# MCU2.net
KiCad netlist of a schematic drawn in Altium Designer
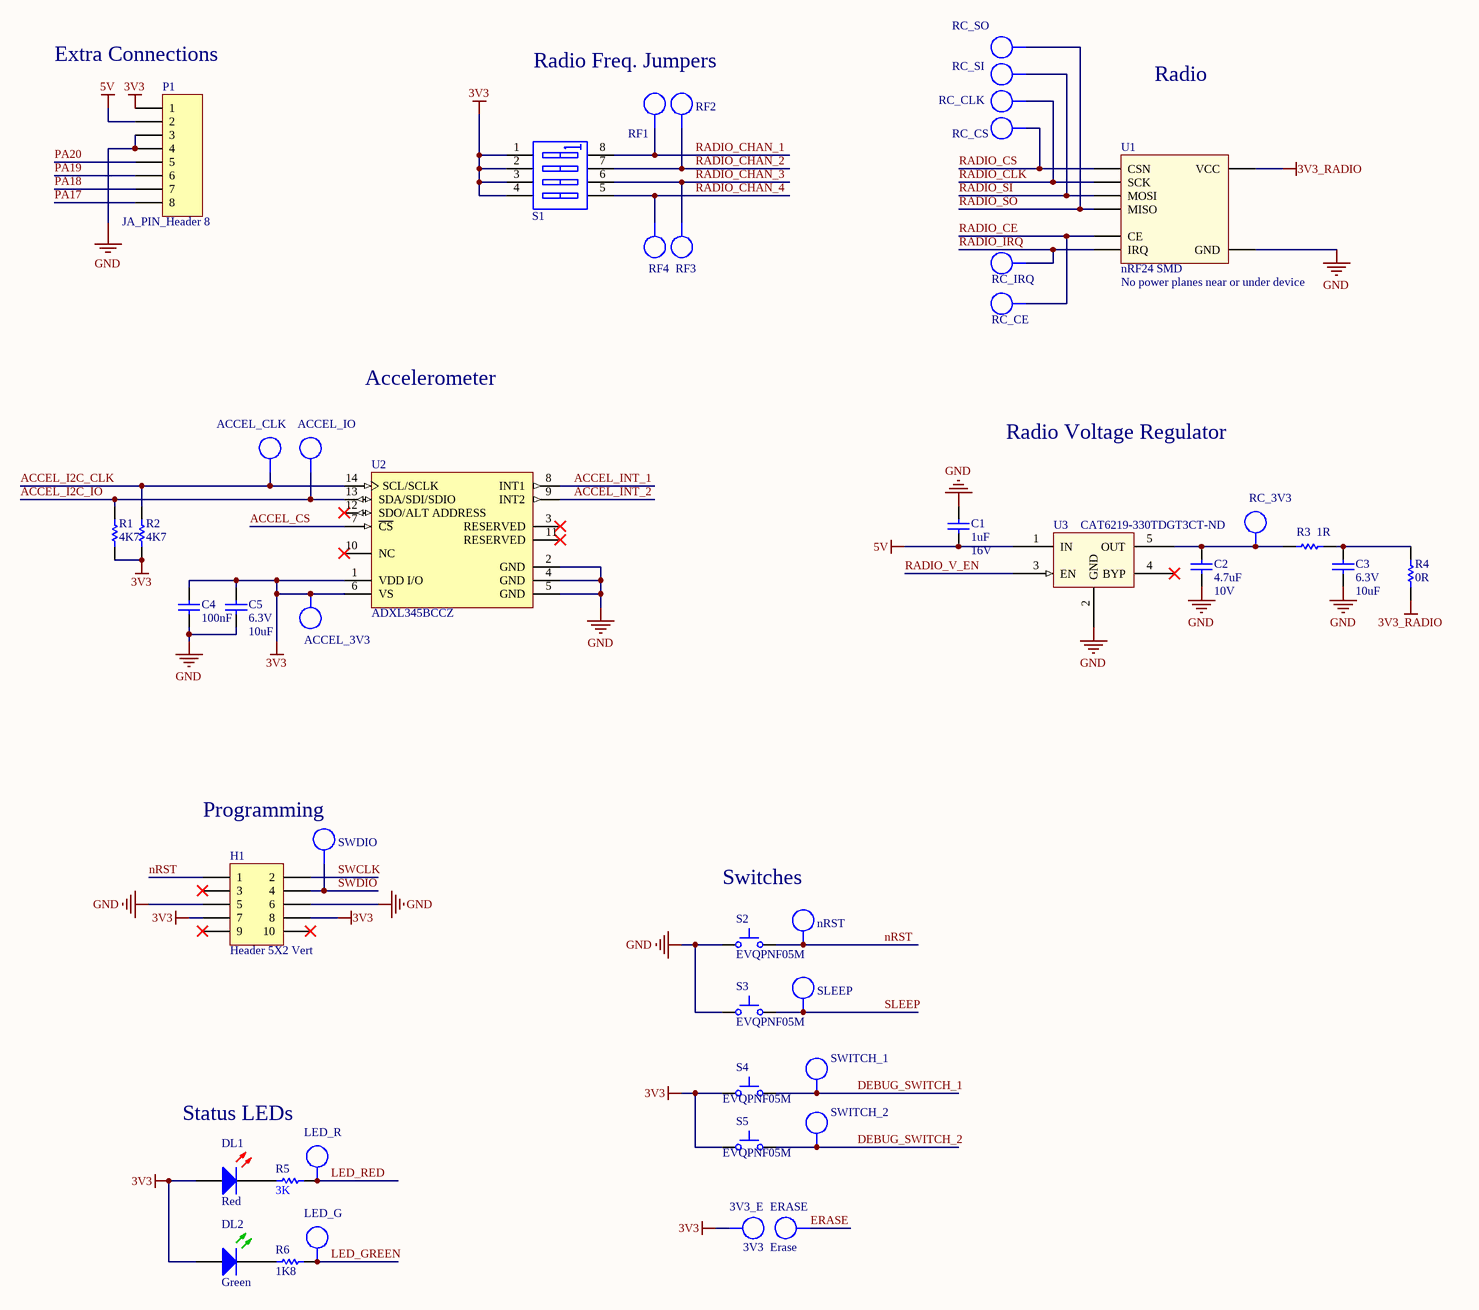
[diagram p0: MCU2.SchDoc]

(export (version "E")
  (design (tool "Eeschema 10.0.6"))
  (components
    (comp (ref "3V3_E")
      (value "3V3")
      (footprint "TP_1206")
      (description "Test-Point 3.3x1.6x2.1mm SMD")
      (fields
        (field (name "MANUFACTURER") "Harwin Inc")
        (field (name "MANUFACTURER PART NUMBER") "S1751-46R")
      )
      (libsource (lib "ECE AD19Components_22V1") (part "TP_1206"))
    )
    (comp (ref "ACCEL_3V3")
      (value "TP")
      (footprint "TP_1206")
      (description "Test-Point 3.3x1.6x2.1mm SMD")
      (fields
        (field (name "MANUFACTURER") "Harwin Inc")
        (field (name "MANUFACTURER PART NUMBER") "S1751-46R")
      )
      (libsource (lib "ECE AD19Components_22V1") (part "TP_1206"))
    )
    (comp (ref "ACCEL_CLK")
      (value "TP")
      (footprint "TP_1206")
      (description "Test-Point 3.3x1.6x2.1mm SMD")
      (fields
        (field (name "MANUFACTURER") "Harwin Inc")
        (field (name "MANUFACTURER PART NUMBER") "S1751-46R")
      )
      (libsource (lib "ECE AD19Components_22V1") (part "TP_1206"))
    )
    (comp (ref "ACCEL_IO")
      (value "TP")
      (footprint "TP_1206")
      (description "Test-Point 3.3x1.6x2.1mm SMD")
      (fields
        (field (name "MANUFACTURER") "Harwin Inc")
        (field (name "MANUFACTURER PART NUMBER") "S1751-46R")
      )
      (libsource (lib "ECE AD19Components_22V1") (part "TP_1206"))
    )
    (comp (ref "C1")
      (value "1uF")
      (footprint "CAPC1608L")
      (description "CAP CER 1uF Y5V -20% +80% 16V 0603")
      (fields (field (name "MAX VOLTAGE") "16V"))
      (libsource (lib "ECE AD19Components_22V1") (part "CC_1uF_0603"))
    )
    (comp (ref "C2")
      (value "4.7uF")
      (footprint "CAPC1608N")
      (description "CAP CER 4.7uF X5R +-20%  10V 0603")
      (fields (field (name "MAX VOLTAGE") "10V"))
      (libsource (lib "ECE AD19Components_22V1") (part "CC_4.7uF_0603"))
    )
    (comp (ref "C3")
      (value "10uF")
      (footprint "CAPC1608L")
      (description "CAP CER 10UF X5R +-20% 6V3 0603")
      (fields (field (name "VOLTAGE - RATED") "6.3V"))
      (libsource (lib "ECE AD19Components_22V1") (part "CC_10uF_0603"))
    )
    (comp (ref "C4")
      (value "100nF")
      (footprint "CAPC1608L")
      (description "CAP CER 100nF X7R +-10% 50V 0603")
      (libsource (lib "ECE AD19Components_22V1") (part "CC_100nF_0603"))
    )
    (comp (ref "C5")
      (value "10uF")
      (footprint "CAPC1608L")
      (description "CAP CER 10UF X5R +-20% 6V3 0603")
      (fields (field (name "VOLTAGE - RATED") "6.3V"))
      (libsource (lib "ECE AD19Components_22V1") (part "CC_10uF_0603"))
    )
    (comp (ref "DL1")
      (value "Red")
      (footprint "WL-SMCW0603")
      (description "LED Red 250mcd 0603 SMD")
      (fields
        (field (name "MANUFACTURER") "WURTH ELEKTRONIK")
        (field (name "MANUFACTURER PART NUMBER") "150060RS75000")
        (field (name "LED COLOUR") "Red")
      )
      (libsource (lib "ECE AD19Components_22V1") (part "DL_150060RS75000"))
    )
    (comp (ref "DL2")
      (value "Green")
      (footprint "WL-SMCW0603")
      (description "LED Green 430mcd 0603 SMD")
      (fields
        (field (name "MANUFACTURER") "WURTH ELEKTRONIK")
        (field (name "MANUFACTURER PART NUMBER") "150060GS75000")
        (field (name "LED COLOUR") "Green")
      )
      (libsource (lib "ECE AD19Components_22V1") (part "DL_150060GS75000"))
    )
    (comp (ref "ERASE")
      (value "Erase")
      (footprint "TP_1206")
      (description "Test-Point 3.3x1.6x2.1mm SMD")
      (fields
        (field (name "MANUFACTURER") "Harwin Inc")
        (field (name "MANUFACTURER PART NUMBER") "S1751-46R")
      )
      (libsource (lib "ECE AD19Components_22V1") (part "TP_1206"))
    )
    (comp (ref "H1")
      (value "Header 5X2 Vert")
      (footprint "IDC2.54-V10D")
      (description "IDC Header, 2,54mm, 10-Pin, Vert")
      (libsource (lib "ECE AD19Components_22V1") (part "JA_HDR_IDC_5X2_VERT"))
    )
    (comp (ref "LED_G")
      (value "TP")
      (footprint "TP_1206")
      (description "Test-Point 3.3x1.6x2.1mm SMD")
      (fields
        (field (name "MANUFACTURER") "Harwin Inc")
        (field (name "MANUFACTURER PART NUMBER") "S1751-46R")
      )
      (libsource (lib "ECE AD19Components_22V1") (part "TP_1206"))
    )
    (comp (ref "LED_R")
      (value "TP")
      (footprint "TP_1206")
      (description "Test-Point 3.3x1.6x2.1mm SMD")
      (fields
        (field (name "MANUFACTURER") "Harwin Inc")
        (field (name "MANUFACTURER PART NUMBER") "S1751-46R")
      )
      (libsource (lib "ECE AD19Components_22V1") (part "TP_1206"))
    )
    (comp (ref "nRST")
      (value "TP")
      (footprint "TP_1206")
      (description "Test-Point 3.3x1.6x2.1mm SMD")
      (fields
        (field (name "MANUFACTURER") "Harwin Inc")
        (field (name "MANUFACTURER PART NUMBER") "S1751-46R")
      )
      (libsource (lib "ECE AD19Components_22V1") (part "TP_1206"))
    )
    (comp (ref "P1")
      (value "JA_PIN_Header 8")
      (footprint "HDR1X8")
      (description "Header, 8-Pin")
      (fields (field (name "PUBLISHER") "Altium Limited"))
      (libsource (lib "ECE AD19Components_22V1") (part "JA_PIN_Header 8"))
    )
    (comp (ref "R1")
      (value "4K7")
      (footprint "RESC1608L")
      (description "RES 4.7K OHM 1/10W 5% 0603 SMD")
      (libsource (lib "ECE AD19Components_22V1") (part "RS_4K7"))
    )
    (comp (ref "R2")
      (value "4K7")
      (footprint "RESC1608L")
      (description "RES 4.7K OHM 1/10W 5% 0603 SMD")
      (libsource (lib "ECE AD19Components_22V1") (part "RS_4K7"))
    )
    (comp (ref "R3")
      (value "1R")
      (footprint "RESC3216L")
      (description "RES 1R OHM 1/4W 5% 1206 SMD")
      (libsource (lib "ECE AD19Components_22V1") (part "RT_1R"))
    )
    (comp (ref "R4")
      (value "0R")
      (footprint "RESC1608L")
      (description "RES 0.0 OHM 1/10W 5% 0603 SMD")
      (libsource (lib "ECE AD19Components_22V1") (part "RS_0R0"))
    )
    (comp (ref "R5")
      (value "3K")
      (footprint "RESC1608L")
      (description "RES 3K OHM 1/10W 5% 0603 SMD")
      (libsource (lib "ECE AD19Components_22V1") (part "RS_3K"))
    )
    (comp (ref "R6")
      (value "1K8")
      (footprint "RESC1608L")
      (description "RES 1.8K OHM 1/10W 5% 0603 SMD")
      (libsource (lib "ECE AD19Components_22V1") (part "RS_1K8"))
    )
    (comp (ref "RC_3V3")
      (value "TP")
      (footprint "TP_1206")
      (description "Test-Point 3.3x1.6x2.1mm SMD")
      (fields
        (field (name "MANUFACTURER") "Harwin Inc")
        (field (name "MANUFACTURER PART NUMBER") "S1751-46R")
      )
      (libsource (lib "ECE AD19Components_22V1") (part "TP_1206"))
    )
    (comp (ref "RC_CE")
      (value "TP")
      (footprint "TP_1206")
      (description "Test-Point 3.3x1.6x2.1mm SMD")
      (fields
        (field (name "MANUFACTURER") "Harwin Inc")
        (field (name "MANUFACTURER PART NUMBER") "S1751-46R")
      )
      (libsource (lib "ECE AD19Components_22V1") (part "TP_1206"))
    )
    (comp (ref "RC_CLK")
      (value "TP")
      (footprint "TP_1206")
      (description "Test-Point 3.3x1.6x2.1mm SMD")
      (fields
        (field (name "MANUFACTURER") "Harwin Inc")
        (field (name "MANUFACTURER PART NUMBER") "S1751-46R")
      )
      (libsource (lib "ECE AD19Components_22V1") (part "TP_1206"))
    )
    (comp (ref "RC_CS")
      (value "TP")
      (footprint "TP_1206")
      (description "Test-Point 3.3x1.6x2.1mm SMD")
      (fields
        (field (name "MANUFACTURER") "Harwin Inc")
        (field (name "MANUFACTURER PART NUMBER") "S1751-46R")
      )
      (libsource (lib "ECE AD19Components_22V1") (part "TP_1206"))
    )
    (comp (ref "RC_IRQ")
      (value "TP")
      (footprint "TP_1206")
      (description "Test-Point 3.3x1.6x2.1mm SMD")
      (fields
        (field (name "MANUFACTURER") "Harwin Inc")
        (field (name "MANUFACTURER PART NUMBER") "S1751-46R")
      )
      (libsource (lib "ECE AD19Components_22V1") (part "TP_1206"))
    )
    (comp (ref "RC_SI")
      (value "TP")
      (footprint "TP_1206")
      (description "Test-Point 3.3x1.6x2.1mm SMD")
      (fields
        (field (name "MANUFACTURER") "Harwin Inc")
        (field (name "MANUFACTURER PART NUMBER") "S1751-46R")
      )
      (libsource (lib "ECE AD19Components_22V1") (part "TP_1206"))
    )
    (comp (ref "RC_SO")
      (value "TP")
      (footprint "TP_1206")
      (description "Test-Point 3.3x1.6x2.1mm SMD")
      (fields
        (field (name "MANUFACTURER") "Harwin Inc")
        (field (name "MANUFACTURER PART NUMBER") "S1751-46R")
      )
      (libsource (lib "ECE AD19Components_22V1") (part "TP_1206"))
    )
    (comp (ref "RF1")
      (value "TP")
      (footprint "TP_1206")
      (description "Test-Point 3.3x1.6x2.1mm SMD")
      (fields
        (field (name "MANUFACTURER") "Harwin Inc")
        (field (name "MANUFACTURER PART NUMBER") "S1751-46R")
      )
      (libsource (lib "ECE AD19Components_22V1") (part "TP_1206"))
    )
    (comp (ref "RF2")
      (value "TP")
      (footprint "TP_1206")
      (description "Test-Point 3.3x1.6x2.1mm SMD")
      (fields
        (field (name "MANUFACTURER") "Harwin Inc")
        (field (name "MANUFACTURER PART NUMBER") "S1751-46R")
      )
      (libsource (lib "ECE AD19Components_22V1") (part "TP_1206"))
    )
    (comp (ref "RF3")
      (value "TP")
      (footprint "TP_1206")
      (description "Test-Point 3.3x1.6x2.1mm SMD")
      (fields
        (field (name "MANUFACTURER") "Harwin Inc")
        (field (name "MANUFACTURER PART NUMBER") "S1751-46R")
      )
      (libsource (lib "ECE AD19Components_22V1") (part "TP_1206"))
    )
    (comp (ref "RF4")
      (value "TP")
      (footprint "TP_1206")
      (description "Test-Point 3.3x1.6x2.1mm SMD")
      (fields
        (field (name "MANUFACTURER") "Harwin Inc")
        (field (name "MANUFACTURER PART NUMBER") "S1751-46R")
      )
      (libsource (lib "ECE AD19Components_22V1") (part "TP_1206"))
    )
    (comp (ref "S1")
      (value "WS_SW DIP-4")
      (footprint "DIP_SW_4WAY_SMD -")
      (description "DIP Switch, 4 Position, SPST SMD")
      (fields
        (field (name "MANUFACTURER") "OMRON ELECTRONIC COMPONENTS")
        (field (name "MANUFACTURER PART NUMBER") "A6SN-4101")
      )
      (libsource (lib "ECE AD19Components_22V1") (part "WS_SW DIP-4"))
    )
    (comp (ref "S2")
      (value "EVQPNF05M")
      (footprint "EVQPNF05M")
      (description "Panasonic 6 x 3.5mm SMD Light Touch Switch Type SMD")
      (fields (field (name "MANUFACTURER") "Panasonic"))
      (libsource (lib "ECE AD19Components_22V1") (part "WS_EVQPNF05M"))
    )
    (comp (ref "S3")
      (value "EVQPNF05M")
      (footprint "EVQPNF05M")
      (description "Panasonic 6 x 3.5mm SMD Light Touch Switch Type SMD")
      (fields (field (name "MANUFACTURER") "Panasonic"))
      (libsource (lib "ECE AD19Components_22V1") (part "WS_EVQPNF05M"))
    )
    (comp (ref "S4")
      (value "EVQPNF05M")
      (footprint "EVQPNF05M")
      (description "Panasonic 6 x 3.5mm SMD Light Touch Switch Type SMD")
      (fields (field (name "MANUFACTURER") "Panasonic"))
      (libsource (lib "ECE AD19Components_22V1") (part "WS_EVQPNF05M"))
    )
    (comp (ref "S5")
      (value "EVQPNF05M")
      (footprint "EVQPNF05M")
      (description "Panasonic 6 x 3.5mm SMD Light Touch Switch Type SMD")
      (fields (field (name "MANUFACTURER") "Panasonic"))
      (libsource (lib "ECE AD19Components_22V1") (part "WS_EVQPNF05M"))
    )
    (comp (ref "SLEEP")
      (value "TP")
      (footprint "TP_1206")
      (description "Test-Point 3.3x1.6x2.1mm SMD")
      (fields
        (field (name "MANUFACTURER") "Harwin Inc")
        (field (name "MANUFACTURER PART NUMBER") "S1751-46R")
      )
      (libsource (lib "ECE AD19Components_22V1") (part "TP_1206"))
    )
    (comp (ref "SWDIO")
      (value "TP")
      (footprint "TP_1206")
      (description "Test-Point 3.3x1.6x2.1mm SMD")
      (fields
        (field (name "MANUFACTURER") "Harwin Inc")
        (field (name "MANUFACTURER PART NUMBER") "S1751-46R")
      )
      (libsource (lib "ECE AD19Components_22V1") (part "TP_1206"))
    )
    (comp (ref "SWITCH_1")
      (value "TP")
      (footprint "TP_1206")
      (description "Test-Point 3.3x1.6x2.1mm SMD")
      (fields
        (field (name "MANUFACTURER") "Harwin Inc")
        (field (name "MANUFACTURER PART NUMBER") "S1751-46R")
      )
      (libsource (lib "ECE AD19Components_22V1") (part "TP_1206"))
    )
    (comp (ref "SWITCH_2")
      (value "TP")
      (footprint "TP_1206")
      (description "Test-Point 3.3x1.6x2.1mm SMD")
      (fields
        (field (name "MANUFACTURER") "Harwin Inc")
        (field (name "MANUFACTURER PART NUMBER") "S1751-46R")
      )
      (libsource (lib "ECE AD19Components_22V1") (part "TP_1206"))
    )
    (comp (ref "U1")
      (value "nRF24 SMD")
      (footprint "NRF24")
      (description "nRF24 SMD Module")
      (fields (field (name "WARNING") "No power planes near or under device"))
      (libsource (lib "ENCE461AD19_V23") (part "NRF24"))
    )
    (comp (ref "U2")
      (value "ADXL345BCCZ")
      (footprint "ADI-CC-14-1_V")
      (fields (field (name "MANUFACTURER") "Analog Devices"))
      (libsource (lib "ENCE461AD19_V23") (part "ADXL345BCCZ"))
    )
    (comp (ref "U3")
      (value "CAT6219-330TDGT3")
      (footprint "SOT95P280X145-5N")
      (description "IC REG LIN 3.3V 500MA TSOT23-5")
      (fields
        (field (name "BASE PART NUMBER") "CAT6219")
        (field (name "SUPPLIER PART NUMBER") "CAT6219-330TDGT3CT-ND")
      )
      (libsource (lib "ENCE461AD19_V23") (part "SV_CAT6219-330TDGT3"))
    )
  )
  (nets
    (net (code "1") (name "/ACCEL_CS") (class "Default")
      (node (ref "U2") (pin "7") (pinfunction "~{CS}_7") (pintype "input"))
    )
    (net (code "2") (name "/ACCEL_I2C_CLK") (class "Default")
      (node (ref "ACCEL_CLK") (pin "1") (pinfunction "1_1") (pintype "passive"))
      (node (ref "R2") (pin "2") (pinfunction "2_2") (pintype "passive"))
      (node (ref "U2") (pin "14") (pinfunction "SCL/SCLK_14") (pintype "input"))
    )
    (net (code "3") (name "/ACCEL_I2C_IO") (class "Default")
      (node (ref "ACCEL_IO") (pin "1") (pinfunction "1_1") (pintype "passive"))
      (node (ref "R1") (pin "2") (pinfunction "2_2") (pintype "passive"))
      (node (ref "U2") (pin "13") (pinfunction "SDA/SDI/SDIO_13") (pintype "bidirectional"))
    )
    (net (code "4") (name "/ACCEL_INT_1") (class "Default")
      (node (ref "U2") (pin "8") (pinfunction "INT1_8") (pintype "output"))
    )
    (net (code "5") (name "/ACCEL_INT_2") (class "Default")
      (node (ref "U2") (pin "9") (pinfunction "INT2_9") (pintype "output"))
    )
    (net (code "6") (name "/DEBUG_SWITCH_1") (class "Default")
      (node (ref "S4") (pin "2") (pintype "passive"))
      (node (ref "SWITCH_1") (pin "1") (pinfunction "1_1") (pintype "passive"))
    )
    (net (code "7") (name "/DEBUG_SWITCH_2") (class "Default")
      (node (ref "S5") (pin "2") (pintype "passive"))
      (node (ref "SWITCH_2") (pin "1") (pinfunction "1_1") (pintype "passive"))
    )
    (net (code "8") (name "/ERASE") (class "Default")
      (node (ref "ERASE") (pin "1") (pinfunction "1_1") (pintype "passive"))
    )
    (net (code "9") (name "/LED_GREEN") (class "Default")
      (node (ref "LED_G") (pin "1") (pinfunction "1_1") (pintype "passive"))
      (node (ref "R6") (pin "2") (pinfunction "2_2") (pintype "passive"))
    )
    (net (code "10") (name "/LED_RED") (class "Default")
      (node (ref "LED_R") (pin "1") (pinfunction "1_1") (pintype "passive"))
      (node (ref "R5") (pin "2") (pinfunction "2_2") (pintype "passive"))
    )
    (net (code "11") (name "/PA17") (class "Default")
      (node (ref "P1") (pin "8") (pinfunction "8_8") (pintype "passive"))
    )
    (net (code "12") (name "/PA18") (class "Default")
      (node (ref "P1") (pin "7") (pinfunction "7_7") (pintype "passive"))
    )
    (net (code "13") (name "/PA19") (class "Default")
      (node (ref "P1") (pin "6") (pinfunction "6_6") (pintype "passive"))
    )
    (net (code "14") (name "/PA20") (class "Default")
      (node (ref "P1") (pin "5") (pinfunction "5_5") (pintype "passive"))
    )
    (net (code "15") (name "/RADIO_CE") (class "Default")
      (node (ref "RC_CE") (pin "1") (pinfunction "1_1") (pintype "passive"))
      (node (ref "U1") (pin "3") (pinfunction "CE_3") (pintype "passive"))
    )
    (net (code "16") (name "/RADIO_CHAN_1") (class "Default")
      (node (ref "RF1") (pin "1") (pinfunction "1_1") (pintype "passive"))
      (node (ref "S1") (pin "8") (pinfunction "B1_8") (pintype "passive"))
    )
    (net (code "17") (name "/RADIO_CHAN_2") (class "Default")
      (node (ref "RF2") (pin "1") (pinfunction "1_1") (pintype "passive"))
      (node (ref "S1") (pin "7") (pinfunction "B2_7") (pintype "passive"))
    )
    (net (code "18") (name "/RADIO_CHAN_3") (class "Default")
      (node (ref "RF3") (pin "1") (pinfunction "1_1") (pintype "passive"))
      (node (ref "S1") (pin "6") (pinfunction "B3_6") (pintype "passive"))
    )
    (net (code "19") (name "/RADIO_CHAN_4") (class "Default")
      (node (ref "RF4") (pin "1") (pinfunction "1_1") (pintype "passive"))
      (node (ref "S1") (pin "5") (pinfunction "B4_5") (pintype "passive"))
    )
    (net (code "20") (name "/RADIO_CLK") (class "Default")
      (node (ref "RC_CLK") (pin "1") (pinfunction "1_1") (pintype "passive"))
      (node (ref "U1") (pin "5") (pinfunction "SCK_5") (pintype "passive"))
    )
    (net (code "21") (name "/RADIO_CS") (class "Default")
      (node (ref "RC_CS") (pin "1") (pinfunction "1_1") (pintype "passive"))
      (node (ref "U1") (pin "4") (pinfunction "CSN_4") (pintype "passive"))
    )
    (net (code "22") (name "/RADIO_IRQ") (class "Default")
      (node (ref "RC_IRQ") (pin "1") (pinfunction "1_1") (pintype "passive"))
      (node (ref "U1") (pin "8") (pinfunction "IRQ_8") (pintype "passive"))
    )
    (net (code "23") (name "/RADIO_SI") (class "Default")
      (node (ref "RC_SI") (pin "1") (pinfunction "1_1") (pintype "passive"))
      (node (ref "U1") (pin "6") (pinfunction "MOSI_6") (pintype "passive"))
    )
    (net (code "24") (name "/RADIO_SO") (class "Default")
      (node (ref "RC_SO") (pin "1") (pinfunction "1_1") (pintype "passive"))
      (node (ref "U1") (pin "7") (pinfunction "MISO_7") (pintype "passive"))
    )
    (net (code "25") (name "/RADIO_V_EN") (class "Default")
      (node (ref "U3") (pin "3") (pinfunction "EN_3") (pintype "input"))
    )
    (net (code "26") (name "/SLEEP") (class "Default")
      (node (ref "S3") (pin "2") (pintype "passive"))
      (node (ref "SLEEP") (pin "1") (pinfunction "1_1") (pintype "passive"))
    )
    (net (code "27") (name "/SWCLK") (class "Default")
      (node (ref "H1") (pin "2") (pinfunction "2_2") (pintype "passive"))
    )
    (net (code "28") (name "/SWDIO") (class "Default")
      (node (ref "H1") (pin "4") (pinfunction "4_4") (pintype "passive"))
      (node (ref "SWDIO") (pin "1") (pinfunction "1_1") (pintype "passive"))
    )
    (net (code "29") (name "/nRST") (class "Default")
      (node (ref "H1") (pin "1") (pinfunction "1_1") (pintype "passive"))
      (node (ref "S2") (pin "2") (pintype "passive"))
      (node (ref "nRST") (pin "1") (pinfunction "1_1") (pintype "passive"))
    )
    (net (code "30") (name "3V3") (class "Default")
      (node (ref "3V3_E") (pin "1") (pinfunction "1_1") (pintype "passive"))
      (node (ref "ACCEL_3V3") (pin "1") (pinfunction "1_1") (pintype "passive"))
      (node (ref "C4") (pin "2") (pinfunction "2_2") (pintype "passive"))
      (node (ref "C5") (pin "2") (pinfunction "2_2") (pintype "passive"))
      (node (ref "DL1") (pin "2") (pinfunction "A_2") (pintype "passive"))
      (node (ref "DL2") (pin "2") (pinfunction "A_2") (pintype "passive"))
      (node (ref "H1") (pin "7") (pinfunction "7_7") (pintype "passive"))
      (node (ref "H1") (pin "8") (pinfunction "8_8") (pintype "passive"))
      (node (ref "P1") (pin "1") (pinfunction "1_1") (pintype "passive"))
      (node (ref "R1") (pin "1") (pinfunction "1_1") (pintype "passive"))
      (node (ref "R2") (pin "1") (pinfunction "1_1") (pintype "passive"))
      (node (ref "S1") (pin "1") (pinfunction "A1_1") (pintype "passive"))
      (node (ref "S1") (pin "2") (pinfunction "A2_2") (pintype "passive"))
      (node (ref "S1") (pin "3") (pinfunction "A3_3") (pintype "passive"))
      (node (ref "S1") (pin "4") (pinfunction "A4_4") (pintype "passive"))
      (node (ref "S4") (pin "1") (pintype "passive"))
      (node (ref "S5") (pin "1") (pintype "passive"))
      (node (ref "U2") (pin "1") (pinfunction "VDD_I/O_1") (pintype "power_in"))
      (node (ref "U2") (pin "6") (pinfunction "VS_6") (pintype "power_in"))
    )
    (net (code "31") (name "3V3_RADIO") (class "Default")
      (node (ref "R4") (pin "1") (pinfunction "1_1") (pintype "passive"))
      (node (ref "U1") (pin "1") (pinfunction "VCC_1") (pintype "passive"))
    )
    (net (code "32") (name "5V") (class "Default")
      (node (ref "C1") (pin "1") (pinfunction "1_1") (pintype "passive"))
      (node (ref "P1") (pin "2") (pinfunction "2_2") (pintype "passive"))
      (node (ref "U3") (pin "1") (pinfunction "IN_1") (pintype "power_in"))
    )
    (net (code "33") (name "GND") (class "Default")
      (node (ref "C1") (pin "2") (pinfunction "2_2") (pintype "passive"))
      (node (ref "C2") (pin "1") (pinfunction "1_1") (pintype "passive"))
      (node (ref "C3") (pin "1") (pinfunction "1_1") (pintype "passive"))
      (node (ref "C4") (pin "1") (pinfunction "1_1") (pintype "passive"))
      (node (ref "C5") (pin "1") (pinfunction "1_1") (pintype "passive"))
      (node (ref "H1") (pin "5") (pinfunction "5_5") (pintype "passive"))
      (node (ref "H1") (pin "6") (pinfunction "6_6") (pintype "passive"))
      (node (ref "P1") (pin "3") (pinfunction "3_3") (pintype "passive"))
      (node (ref "P1") (pin "4") (pinfunction "4_4") (pintype "passive"))
      (node (ref "S2") (pin "1") (pintype "passive"))
      (node (ref "S3") (pin "1") (pintype "passive"))
      (node (ref "U1") (pin "2") (pinfunction "GND_2") (pintype "passive"))
      (node (ref "U2") (pin "2") (pinfunction "GND_2") (pintype "power_in"))
      (node (ref "U2") (pin "4") (pinfunction "GND_4") (pintype "power_in"))
      (node (ref "U2") (pin "5") (pinfunction "GND_5") (pintype "power_in"))
      (node (ref "U3") (pin "2") (pinfunction "GND_2") (pintype "power_in"))
    )
    (net (code "34") (name "Net-(C3-Pad2)") (class "Default")
      (node (ref "C3") (pin "2") (pinfunction "2_2") (pintype "passive"))
      (node (ref "R3") (pin "2") (pinfunction "2_2") (pintype "passive"))
      (node (ref "R4") (pin "2") (pinfunction "2_2") (pintype "passive"))
    )
    (net (code "35") (name "Net-(DL1-K)") (class "Default")
      (node (ref "DL1") (pin "1") (pinfunction "K_1") (pintype "passive"))
      (node (ref "R5") (pin "1") (pinfunction "1_1") (pintype "passive"))
    )
    (net (code "36") (name "Net-(DL2-K)") (class "Default")
      (node (ref "DL2") (pin "1") (pinfunction "K_1") (pintype "passive"))
      (node (ref "R6") (pin "1") (pinfunction "1_1") (pintype "passive"))
    )
    (net (code "37") (name "Net-(U3-OUT)") (class "Default")
      (node (ref "C2") (pin "2") (pinfunction "2_2") (pintype "passive"))
      (node (ref "R3") (pin "1") (pinfunction "1_1") (pintype "passive"))
      (node (ref "RC_3V3") (pin "1") (pinfunction "1_1") (pintype "passive"))
      (node (ref "U3") (pin "5") (pinfunction "OUT_5") (pintype "power_in"))
    )
    (net (code "38") (name "unconnected-(H1-Pad3)") (class "Default")
      (node (ref "H1") (pin "3") (pinfunction "3_3") (pintype "passive+no_connect"))
    )
    (net (code "39") (name "unconnected-(H1-Pad9)") (class "Default")
      (node (ref "H1") (pin "9") (pinfunction "9_9") (pintype "passive+no_connect"))
    )
    (net (code "40") (name "unconnected-(H1-Pad10)") (class "Default")
      (node (ref "H1") (pin "10") (pinfunction "10_10") (pintype "passive+no_connect"))
    )
    (net (code "41") (name "unconnected-(U2-NC-Pad10)") (class "Default")
      (node (ref "U2") (pin "10") (pinfunction "NC_10") (pintype "passive+no_connect"))
    )
    (net (code "42") (name "unconnected-(U2-RESERVED-Pad3)") (class "Default")
      (node (ref "U2") (pin "3") (pinfunction "RESERVED_3") (pintype "passive+no_connect"))
    )
    (net (code "43") (name "unconnected-(U2-RESERVED-Pad11)") (class "Default")
      (node (ref "U2") (pin "11") (pinfunction "RESERVED_11") (pintype "passive+no_connect"))
    )
    (net (code "44") (name "unconnected-(U2-SDO{slash}ALT_ADDRESS-Pad12)") (class "Default")
      (node (ref "U2") (pin "12") (pinfunction "SDO/ALT_ADDRESS_12") (pintype "bidirectional+no_connect"))
    )
    (net (code "45") (name "unconnected-(U3-BYP-Pad4)") (class "Default")
      (node (ref "U3") (pin "4") (pinfunction "BYP_4") (pintype "passive+no_connect"))
    )
  )
)
